# ArduinoDue.net
KiCad netlist of a schematic drawn in Altium Designer
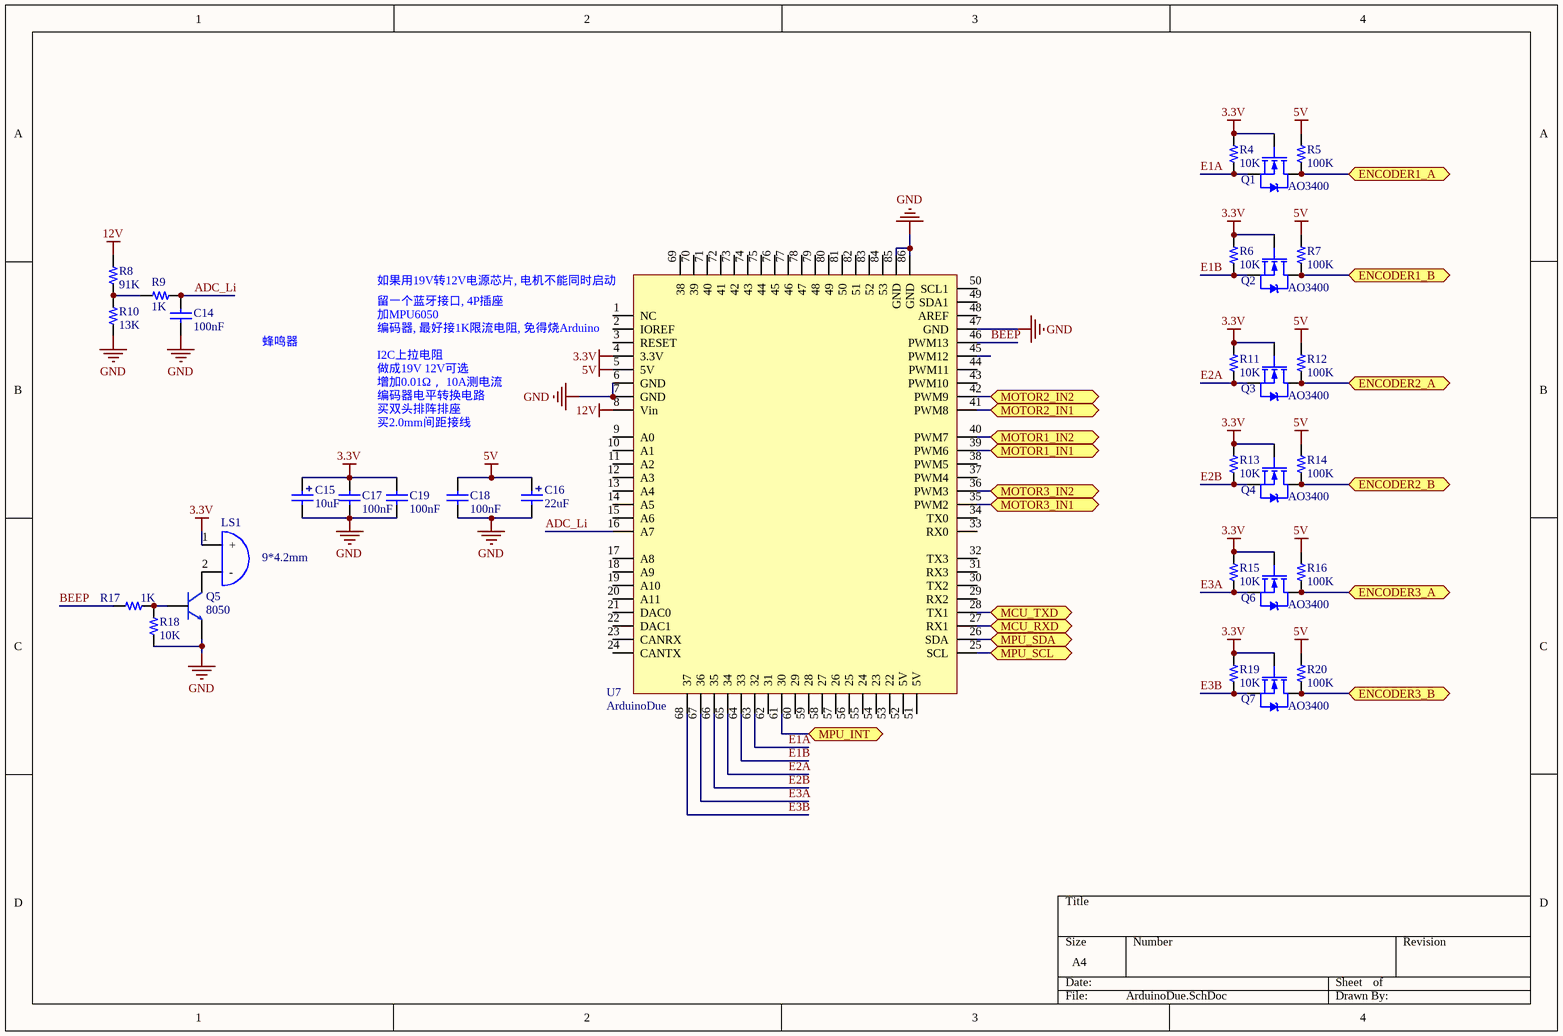
[diagram p0: ArduinoDue.SchDoc]

(export (version "E")
  (design (tool "Eeschema 10.0.6"))
  (components
    (comp (ref "C14")
      (value "100nF")
      (footprint "dq - 0402")
      (description "Capacitor")
      (fields (field (name "Comment") "Cap") (field (name "PUBLISHER") "Altium Limited"))
      (libsource (lib "weifengdq") (part "DQ_Cap"))
    )
    (comp (ref "C15")
      (value "10uF")
      (footprint "3216-18")
      (description "Capacitor")
      (fields (field (name "Comment") "Cap_Pol") (field (name "PUBLISHER") "Altium Limited"))
      (libsource (lib "weifengdq") (part "Cap_Pol"))
    )
    (comp (ref "C16")
      (value "22uF")
      (footprint "3528-21")
      (description "Capacitor")
      (fields (field (name "Comment") "Cap_Pol") (field (name "PUBLISHER") "Altium Limited"))
      (libsource (lib "weifengdq") (part "Cap_Pol"))
    )
    (comp (ref "C17")
      (value "100nF")
      (footprint "dq - 0402")
      (description "Capacitor")
      (fields (field (name "Comment") "Cap") (field (name "PUBLISHER") "Altium Limited"))
      (libsource (lib "weifengdq") (part "DQ_Cap"))
    )
    (comp (ref "C18")
      (value "100nF")
      (footprint "dq - 0402")
      (description "Capacitor")
      (fields (field (name "Comment") "Cap") (field (name "PUBLISHER") "Altium Limited"))
      (libsource (lib "weifengdq") (part "DQ_Cap"))
    )
    (comp (ref "C19")
      (value "100nF")
      (footprint "dq - 0402")
      (description "Capacitor")
      (fields (field (name "Comment") "Cap") (field (name "PUBLISHER") "Altium Limited"))
      (libsource (lib "weifengdq") (part "DQ_Cap"))
    )
    (comp (ref "LS1")
      (value "9*4.2mm")
      (footprint "BUZZER-9*4.2MM")
      (description "Electrical Bell")
      (fields (field (name "PUBLISHER") "Altium Limited"))
      (libsource (lib "weifengdq") (part "Buzzer_1"))
    )
    (comp (ref "Q1")
      (value "AO3400")
      (footprint "SOT-23-3 - AO3400")
      (description "N-Channel Power MOSFET")
      (fields (field (name "PUBLISHER") "Altium Limited"))
      (libsource (lib "weifengdq") (part "NMOS"))
    )
    (comp (ref "Q2")
      (value "AO3400")
      (footprint "SOT-23-3 - AO3400")
      (description "N-Channel Power MOSFET")
      (fields (field (name "PUBLISHER") "Altium Limited"))
      (libsource (lib "weifengdq") (part "NMOS"))
    )
    (comp (ref "Q3")
      (value "AO3400")
      (footprint "SOT-23-3 - AO3400")
      (description "N-Channel Power MOSFET")
      (fields (field (name "PUBLISHER") "Altium Limited"))
      (libsource (lib "weifengdq") (part "NMOS"))
    )
    (comp (ref "Q4")
      (value "AO3400")
      (footprint "SOT-23-3 - AO3400")
      (description "N-Channel Power MOSFET")
      (fields (field (name "PUBLISHER") "Altium Limited"))
      (libsource (lib "weifengdq") (part "NMOS"))
    )
    (comp (ref "Q5") (value "8050") (footprint "SOT-23-3") (libsource (lib "weifengdq") (part "NPN")))
    (comp (ref "Q6")
      (value "AO3400")
      (footprint "SOT-23-3 - AO3400")
      (description "N-Channel Power MOSFET")
      (fields (field (name "PUBLISHER") "Altium Limited"))
      (libsource (lib "weifengdq") (part "NMOS"))
    )
    (comp (ref "Q7")
      (value "AO3400")
      (footprint "SOT-23-3 - AO3400")
      (description "N-Channel Power MOSFET")
      (fields (field (name "PUBLISHER") "Altium Limited"))
      (libsource (lib "weifengdq") (part "NMOS"))
    )
    (comp (ref "R4")
      (value "10K")
      (footprint "dq - 0402")
      (description "Resistance")
      (fields (field (name "Comment") "Res"))
      (libsource (lib "weifengdq") (part "DQ_Res"))
    )
    (comp (ref "R5")
      (value "100K")
      (footprint "dq - 0402")
      (description "Resistance")
      (fields (field (name "Comment") "Res"))
      (libsource (lib "weifengdq") (part "DQ_Res"))
    )
    (comp (ref "R6")
      (value "10K")
      (footprint "dq - 0402")
      (description "Resistance")
      (fields (field (name "Comment") "Res"))
      (libsource (lib "weifengdq") (part "DQ_Res"))
    )
    (comp (ref "R7")
      (value "100K")
      (footprint "dq - 0402")
      (description "Resistance")
      (fields (field (name "Comment") "Res"))
      (libsource (lib "weifengdq") (part "DQ_Res"))
    )
    (comp (ref "R8")
      (value "91K")
      (footprint "dq - 0402")
      (description "Resistance")
      (fields (field (name "Comment") "Res"))
      (libsource (lib "weifengdq") (part "DQ_Res"))
    )
    (comp (ref "R9")
      (value "1K")
      (footprint "dq - 0402")
      (description "Resistance")
      (fields (field (name "Comment") "Res"))
      (libsource (lib "weifengdq") (part "DQ_Res"))
    )
    (comp (ref "R10")
      (value "13K")
      (footprint "dq - 0402")
      (description "Resistance")
      (fields (field (name "Comment") "Res"))
      (libsource (lib "weifengdq") (part "DQ_Res"))
    )
    (comp (ref "R11")
      (value "10K")
      (footprint "dq - 0402")
      (description "Resistance")
      (fields (field (name "Comment") "Res"))
      (libsource (lib "weifengdq") (part "DQ_Res"))
    )
    (comp (ref "R12")
      (value "100K")
      (footprint "dq - 0402")
      (description "Resistance")
      (fields (field (name "Comment") "Res"))
      (libsource (lib "weifengdq") (part "DQ_Res"))
    )
    (comp (ref "R13")
      (value "10K")
      (footprint "dq - 0402")
      (description "Resistance")
      (fields (field (name "Comment") "Res"))
      (libsource (lib "weifengdq") (part "DQ_Res"))
    )
    (comp (ref "R14")
      (value "100K")
      (footprint "dq - 0402")
      (description "Resistance")
      (fields (field (name "Comment") "Res"))
      (libsource (lib "weifengdq") (part "DQ_Res"))
    )
    (comp (ref "R15")
      (value "10K")
      (footprint "dq - 0402")
      (description "Resistance")
      (fields (field (name "Comment") "Res"))
      (libsource (lib "weifengdq") (part "DQ_Res"))
    )
    (comp (ref "R16")
      (value "100K")
      (footprint "dq - 0402")
      (description "Resistance")
      (fields (field (name "Comment") "Res"))
      (libsource (lib "weifengdq") (part "DQ_Res"))
    )
    (comp (ref "R17")
      (value "1K")
      (footprint "dq - 0402")
      (description "Resistance")
      (fields (field (name "Comment") "Res"))
      (libsource (lib "weifengdq") (part "DQ_Res"))
    )
    (comp (ref "R18")
      (value "10K")
      (footprint "dq - 0402")
      (description "Resistance")
      (fields (field (name "Comment") "Res"))
      (libsource (lib "weifengdq") (part "DQ_Res"))
    )
    (comp (ref "R19")
      (value "10K")
      (footprint "dq - 0402")
      (description "Resistance")
      (fields (field (name "Comment") "Res"))
      (libsource (lib "weifengdq") (part "DQ_Res"))
    )
    (comp (ref "R20")
      (value "100K")
      (footprint "dq - 0402")
      (description "Resistance")
      (fields (field (name "Comment") "Res"))
      (libsource (lib "weifengdq") (part "DQ_Res"))
    )
    (comp (ref "U7")
      (value "ArduinoDue")
      (footprint "ArduinoDue")
      (libsource (lib "weifengdq") (part "ArduinoDue"))
    )
  )
  (nets
    (net (code "1") (name "/ADC_Li") (class "Default")
      (node (ref "C14") (pin "2") (pinfunction "2_2") (pintype "passive"))
      (node (ref "R9") (pin "2") (pintype "passive"))
      (node (ref "U7") (pin "16") (pinfunction "A7_16") (pintype "passive"))
    )
    (net (code "2") (name "/BEEP") (class "Default")
      (node (ref "R17") (pin "2") (pintype "passive"))
      (node (ref "U7") (pin "46") (pinfunction "PWM13_46") (pintype "passive"))
    )
    (net (code "3") (name "/E1A") (class "Default")
      (node (ref "Q1") (pin "3") (pinfunction "S_3") (pintype "passive"))
      (node (ref "R4") (pin "2") (pintype "passive"))
      (node (ref "U7") (pin "63") (pinfunction "32_63") (pintype "passive"))
    )
    (net (code "4") (name "/E1B") (class "Default")
      (node (ref "Q2") (pin "3") (pinfunction "S_3") (pintype "passive"))
      (node (ref "R6") (pin "2") (pintype "passive"))
      (node (ref "U7") (pin "64") (pinfunction "33_64") (pintype "passive"))
    )
    (net (code "5") (name "/E2A") (class "Default")
      (node (ref "Q3") (pin "3") (pinfunction "S_3") (pintype "passive"))
      (node (ref "R11") (pin "2") (pintype "passive"))
      (node (ref "U7") (pin "65") (pinfunction "34_65") (pintype "passive"))
    )
    (net (code "6") (name "/E2B") (class "Default")
      (node (ref "Q4") (pin "3") (pinfunction "S_3") (pintype "passive"))
      (node (ref "R13") (pin "2") (pintype "passive"))
      (node (ref "U7") (pin "66") (pinfunction "35_66") (pintype "passive"))
    )
    (net (code "7") (name "/E3A") (class "Default")
      (node (ref "Q6") (pin "3") (pinfunction "S_3") (pintype "passive"))
      (node (ref "R15") (pin "2") (pintype "passive"))
      (node (ref "U7") (pin "67") (pinfunction "36_67") (pintype "passive"))
    )
    (net (code "8") (name "/E3B") (class "Default")
      (node (ref "Q7") (pin "3") (pinfunction "S_3") (pintype "passive"))
      (node (ref "R19") (pin "2") (pintype "passive"))
      (node (ref "U7") (pin "68") (pinfunction "37_68") (pintype "passive"))
    )
    (net (code "9") (name "/ENCODER1_A") (class "Default")
      (node (ref "Q1") (pin "2") (pinfunction "D_2") (pintype "passive"))
      (node (ref "R5") (pin "2") (pintype "passive"))
    )
    (net (code "10") (name "/ENCODER1_B") (class "Default")
      (node (ref "Q2") (pin "2") (pinfunction "D_2") (pintype "passive"))
      (node (ref "R7") (pin "2") (pintype "passive"))
    )
    (net (code "11") (name "/ENCODER2_A") (class "Default")
      (node (ref "Q3") (pin "2") (pinfunction "D_2") (pintype "passive"))
      (node (ref "R12") (pin "2") (pintype "passive"))
    )
    (net (code "12") (name "/ENCODER2_B") (class "Default")
      (node (ref "Q4") (pin "2") (pinfunction "D_2") (pintype "passive"))
      (node (ref "R14") (pin "2") (pintype "passive"))
    )
    (net (code "13") (name "/ENCODER3_A") (class "Default")
      (node (ref "Q6") (pin "2") (pinfunction "D_2") (pintype "passive"))
      (node (ref "R16") (pin "2") (pintype "passive"))
    )
    (net (code "14") (name "/ENCODER3_B") (class "Default")
      (node (ref "Q7") (pin "2") (pinfunction "D_2") (pintype "passive"))
      (node (ref "R20") (pin "2") (pintype "passive"))
    )
    (net (code "15") (name "/MCU_RXD") (class "Default")
      (node (ref "U7") (pin "27") (pinfunction "RX1_27") (pintype "passive"))
    )
    (net (code "16") (name "/MCU_TXD") (class "Default")
      (node (ref "U7") (pin "28") (pinfunction "TX1_28") (pintype "passive"))
    )
    (net (code "17") (name "/MOTOR1_IN1") (class "Default")
      (node (ref "U7") (pin "39") (pinfunction "PWM6_39") (pintype "passive"))
    )
    (net (code "18") (name "/MOTOR1_IN2") (class "Default")
      (node (ref "U7") (pin "40") (pinfunction "PWM7_40") (pintype "passive"))
    )
    (net (code "19") (name "/MOTOR2_IN1") (class "Default")
      (node (ref "U7") (pin "41") (pinfunction "PWM8_41") (pintype "passive"))
    )
    (net (code "20") (name "/MOTOR2_IN2") (class "Default")
      (node (ref "U7") (pin "42") (pinfunction "PWM9_42") (pintype "passive"))
    )
    (net (code "21") (name "/MOTOR3_IN1") (class "Default")
      (node (ref "U7") (pin "35") (pinfunction "PWM2_35") (pintype "passive"))
    )
    (net (code "22") (name "/MOTOR3_IN2") (class "Default")
      (node (ref "U7") (pin "36") (pinfunction "PWM3_36") (pintype "passive"))
    )
    (net (code "23") (name "/MPU_INT") (class "Default")
      (node (ref "U7") (pin "61") (pinfunction "30_61") (pintype "passive"))
    )
    (net (code "24") (name "/MPU_SCL") (class "Default")
      (node (ref "U7") (pin "25") (pinfunction "SCL_25") (pintype "passive"))
    )
    (net (code "25") (name "/MPU_SDA") (class "Default")
      (node (ref "U7") (pin "26") (pinfunction "SDA_26") (pintype "passive"))
    )
    (net (code "26") (name "3.3V") (class "Default")
      (node (ref "C15") (pin "1") (pinfunction "1_1") (pintype "passive"))
      (node (ref "C17") (pin "2") (pinfunction "2_2") (pintype "passive"))
      (node (ref "C19") (pin "2") (pinfunction "2_2") (pintype "passive"))
      (node (ref "LS1") (pin "1") (pinfunction "+_1") (pintype "passive"))
      (node (ref "Q1") (pin "1") (pinfunction "G_1") (pintype "passive"))
      (node (ref "Q2") (pin "1") (pinfunction "G_1") (pintype "passive"))
      (node (ref "Q3") (pin "1") (pinfunction "G_1") (pintype "passive"))
      (node (ref "Q4") (pin "1") (pinfunction "G_1") (pintype "passive"))
      (node (ref "Q6") (pin "1") (pinfunction "G_1") (pintype "passive"))
      (node (ref "Q7") (pin "1") (pinfunction "G_1") (pintype "passive"))
      (node (ref "R11") (pin "1") (pintype "passive"))
      (node (ref "R13") (pin "1") (pintype "passive"))
      (node (ref "R15") (pin "1") (pintype "passive"))
      (node (ref "R19") (pin "1") (pintype "passive"))
      (node (ref "R4") (pin "1") (pintype "passive"))
      (node (ref "R6") (pin "1") (pintype "passive"))
      (node (ref "U7") (pin "4") (pinfunction "3.3V_4") (pintype "passive"))
    )
    (net (code "27") (name "5V") (class "Default")
      (node (ref "C16") (pin "1") (pinfunction "1_1") (pintype "passive"))
      (node (ref "C18") (pin "2") (pinfunction "2_2") (pintype "passive"))
      (node (ref "R12") (pin "1") (pintype "passive"))
      (node (ref "R14") (pin "1") (pintype "passive"))
      (node (ref "R16") (pin "1") (pintype "passive"))
      (node (ref "R20") (pin "1") (pintype "passive"))
      (node (ref "R5") (pin "1") (pintype "passive"))
      (node (ref "R7") (pin "1") (pintype "passive"))
      (node (ref "U7") (pin "5") (pinfunction "5V_5") (pintype "passive"))
    )
    (net (code "28") (name "12V") (class "Default")
      (node (ref "R8") (pin "1") (pintype "passive"))
      (node (ref "U7") (pin "8") (pinfunction "Vin_8") (pintype "passive"))
    )
    (net (code "29") (name "GND") (class "Default")
      (node (ref "C14") (pin "1") (pinfunction "1_1") (pintype "passive"))
      (node (ref "C15") (pin "2") (pinfunction "2_2") (pintype "passive"))
      (node (ref "C16") (pin "2") (pinfunction "2_2") (pintype "passive"))
      (node (ref "C17") (pin "1") (pinfunction "1_1") (pintype "passive"))
      (node (ref "C18") (pin "1") (pinfunction "1_1") (pintype "passive"))
      (node (ref "C19") (pin "1") (pinfunction "1_1") (pintype "passive"))
      (node (ref "Q5") (pin "1") (pinfunction "e_1") (pintype "passive"))
      (node (ref "R10") (pin "2") (pintype "passive"))
      (node (ref "R18") (pin "2") (pintype "passive"))
      (node (ref "U7") (pin "47") (pinfunction "GND_47") (pintype "passive"))
      (node (ref "U7") (pin "6") (pinfunction "GND_6") (pintype "passive"))
      (node (ref "U7") (pin "7") (pinfunction "GND_7") (pintype "passive"))
      (node (ref "U7") (pin "85") (pinfunction "GND_85") (pintype "passive"))
      (node (ref "U7") (pin "86") (pinfunction "GND_86") (pintype "passive"))
    )
    (net (code "30") (name "Net-(LS1--)") (class "Default")
      (node (ref "LS1") (pin "2") (pinfunction "-_2") (pintype "passive"))
      (node (ref "Q5") (pin "3") (pinfunction "c_3") (pintype "passive"))
    )
    (net (code "31") (name "Net-(Q5-b)") (class "Default")
      (node (ref "Q5") (pin "2") (pinfunction "b_2") (pintype "passive"))
      (node (ref "R17") (pin "1") (pintype "passive"))
      (node (ref "R18") (pin "1") (pintype "passive"))
    )
    (net (code "32") (name "Net-(R10-Pad1)") (class "Default")
      (node (ref "R10") (pin "1") (pintype "passive"))
      (node (ref "R8") (pin "2") (pintype "passive"))
      (node (ref "R9") (pin "1") (pintype "passive"))
    )
    (net (code "33") (name "unconnected-(U7-5V-Pad51)") (class "Default")
      (node (ref "U7") (pin "51") (pinfunction "5V_51") (pintype "passive"))
    )
    (net (code "34") (name "unconnected-(U7-5V-Pad52)") (class "Default")
      (node (ref "U7") (pin "52") (pinfunction "5V_52") (pintype "passive"))
    )
    (net (code "35") (name "unconnected-(U7-22-Pad53)") (class "Default")
      (node (ref "U7") (pin "53") (pinfunction "22_53") (pintype "passive"))
    )
    (net (code "36") (name "unconnected-(U7-23-Pad54)") (class "Default")
      (node (ref "U7") (pin "54") (pinfunction "23_54") (pintype "passive"))
    )
    (net (code "37") (name "unconnected-(U7-24-Pad55)") (class "Default")
      (node (ref "U7") (pin "55") (pinfunction "24_55") (pintype "passive"))
    )
    (net (code "38") (name "unconnected-(U7-25-Pad56)") (class "Default")
      (node (ref "U7") (pin "56") (pinfunction "25_56") (pintype "passive"))
    )
    (net (code "39") (name "unconnected-(U7-26-Pad57)") (class "Default")
      (node (ref "U7") (pin "57") (pinfunction "26_57") (pintype "passive"))
    )
    (net (code "40") (name "unconnected-(U7-27-Pad58)") (class "Default")
      (node (ref "U7") (pin "58") (pinfunction "27_58") (pintype "passive"))
    )
    (net (code "41") (name "unconnected-(U7-28-Pad59)") (class "Default")
      (node (ref "U7") (pin "59") (pinfunction "28_59") (pintype "passive"))
    )
    (net (code "42") (name "unconnected-(U7-29-Pad60)") (class "Default")
      (node (ref "U7") (pin "60") (pinfunction "29_60") (pintype "passive"))
    )
    (net (code "43") (name "unconnected-(U7-31-Pad62)") (class "Default")
      (node (ref "U7") (pin "62") (pinfunction "31_62") (pintype "passive"))
    )
    (net (code "44") (name "unconnected-(U7-38-Pad69)") (class "Default")
      (node (ref "U7") (pin "69") (pinfunction "38_69") (pintype "passive"))
    )
    (net (code "45") (name "unconnected-(U7-39-Pad70)") (class "Default")
      (node (ref "U7") (pin "70") (pinfunction "39_70") (pintype "passive"))
    )
    (net (code "46") (name "unconnected-(U7-40-Pad71)") (class "Default")
      (node (ref "U7") (pin "71") (pinfunction "40_71") (pintype "passive"))
    )
    (net (code "47") (name "unconnected-(U7-41-Pad72)") (class "Default")
      (node (ref "U7") (pin "72") (pinfunction "41_72") (pintype "passive"))
    )
    (net (code "48") (name "unconnected-(U7-42-Pad73)") (class "Default")
      (node (ref "U7") (pin "73") (pinfunction "42_73") (pintype "passive"))
    )
    (net (code "49") (name "unconnected-(U7-43-Pad74)") (class "Default")
      (node (ref "U7") (pin "74") (pinfunction "43_74") (pintype "passive"))
    )
    (net (code "50") (name "unconnected-(U7-44-Pad75)") (class "Default")
      (node (ref "U7") (pin "75") (pinfunction "44_75") (pintype "passive"))
    )
    (net (code "51") (name "unconnected-(U7-45-Pad76)") (class "Default")
      (node (ref "U7") (pin "76") (pinfunction "45_76") (pintype "passive"))
    )
    (net (code "52") (name "unconnected-(U7-46-Pad77)") (class "Default")
      (node (ref "U7") (pin "77") (pinfunction "46_77") (pintype "passive"))
    )
    (net (code "53") (name "unconnected-(U7-47-Pad78)") (class "Default")
      (node (ref "U7") (pin "78") (pinfunction "47_78") (pintype "passive"))
    )
    (net (code "54") (name "unconnected-(U7-48-Pad79)") (class "Default")
      (node (ref "U7") (pin "79") (pinfunction "48_79") (pintype "passive"))
    )
    (net (code "55") (name "unconnected-(U7-49-Pad80)") (class "Default")
      (node (ref "U7") (pin "80") (pinfunction "49_80") (pintype "passive"))
    )
    (net (code "56") (name "unconnected-(U7-50-Pad81)") (class "Default")
      (node (ref "U7") (pin "81") (pinfunction "50_81") (pintype "passive"))
    )
    (net (code "57") (name "unconnected-(U7-51-Pad82)") (class "Default")
      (node (ref "U7") (pin "82") (pinfunction "51_82") (pintype "passive"))
    )
    (net (code "58") (name "unconnected-(U7-52-Pad83)") (class "Default")
      (node (ref "U7") (pin "83") (pinfunction "52_83") (pintype "passive"))
    )
    (net (code "59") (name "unconnected-(U7-53-Pad84)") (class "Default")
      (node (ref "U7") (pin "84") (pinfunction "53_84") (pintype "passive"))
    )
    (net (code "60") (name "unconnected-(U7-A0-Pad9)") (class "Default")
      (node (ref "U7") (pin "9") (pinfunction "A0_9") (pintype "passive"))
    )
    (net (code "61") (name "unconnected-(U7-A1-Pad10)") (class "Default")
      (node (ref "U7") (pin "10") (pinfunction "A1_10") (pintype "passive"))
    )
    (net (code "62") (name "unconnected-(U7-A2-Pad11)") (class "Default")
      (node (ref "U7") (pin "11") (pinfunction "A2_11") (pintype "passive"))
    )
    (net (code "63") (name "unconnected-(U7-A3-Pad12)") (class "Default")
      (node (ref "U7") (pin "12") (pinfunction "A3_12") (pintype "passive"))
    )
    (net (code "64") (name "unconnected-(U7-A4-Pad13)") (class "Default")
      (node (ref "U7") (pin "13") (pinfunction "A4_13") (pintype "passive"))
    )
    (net (code "65") (name "unconnected-(U7-A5-Pad14)") (class "Default")
      (node (ref "U7") (pin "14") (pinfunction "A5_14") (pintype "passive"))
    )
    (net (code "66") (name "unconnected-(U7-A6-Pad15)") (class "Default")
      (node (ref "U7") (pin "15") (pinfunction "A6_15") (pintype "passive"))
    )
    (net (code "67") (name "unconnected-(U7-A8-Pad17)") (class "Default")
      (node (ref "U7") (pin "17") (pinfunction "A8_17") (pintype "passive"))
    )
    (net (code "68") (name "unconnected-(U7-A9-Pad18)") (class "Default")
      (node (ref "U7") (pin "18") (pinfunction "A9_18") (pintype "passive"))
    )
    (net (code "69") (name "unconnected-(U7-A10-Pad19)") (class "Default")
      (node (ref "U7") (pin "19") (pinfunction "A10_19") (pintype "passive"))
    )
    (net (code "70") (name "unconnected-(U7-A11-Pad20)") (class "Default")
      (node (ref "U7") (pin "20") (pinfunction "A11_20") (pintype "passive"))
    )
    (net (code "71") (name "unconnected-(U7-AREF-Pad48)") (class "Default")
      (node (ref "U7") (pin "48") (pinfunction "AREF_48") (pintype "passive"))
    )
    (net (code "72") (name "unconnected-(U7-CANRX-Pad23)") (class "Default")
      (node (ref "U7") (pin "23") (pinfunction "CANRX_23") (pintype "passive"))
    )
    (net (code "73") (name "unconnected-(U7-CANTX-Pad24)") (class "Default")
      (node (ref "U7") (pin "24") (pinfunction "CANTX_24") (pintype "passive"))
    )
    (net (code "74") (name "unconnected-(U7-DAC0-Pad21)") (class "Default")
      (node (ref "U7") (pin "21") (pinfunction "DAC0_21") (pintype "passive"))
    )
    (net (code "75") (name "unconnected-(U7-DAC1-Pad22)") (class "Default")
      (node (ref "U7") (pin "22") (pinfunction "DAC1_22") (pintype "passive"))
    )
    (net (code "76") (name "unconnected-(U7-IOREF-Pad2)") (class "Default")
      (node (ref "U7") (pin "2") (pinfunction "IOREF_2") (pintype "passive"))
    )
    (net (code "77") (name "unconnected-(U7-NC-Pad1)") (class "Default")
      (node (ref "U7") (pin "1") (pinfunction "NC_1") (pintype "passive"))
    )
    (net (code "78") (name "unconnected-(U7-PWM4-Pad37)") (class "Default")
      (node (ref "U7") (pin "37") (pinfunction "PWM4_37") (pintype "passive"))
    )
    (net (code "79") (name "unconnected-(U7-PWM5-Pad38)") (class "Default")
      (node (ref "U7") (pin "38") (pinfunction "PWM5_38") (pintype "passive"))
    )
    (net (code "80") (name "unconnected-(U7-PWM10-Pad43)") (class "Default")
      (node (ref "U7") (pin "43") (pinfunction "PWM10_43") (pintype "passive"))
    )
    (net (code "81") (name "unconnected-(U7-PWM11-Pad44)") (class "Default")
      (node (ref "U7") (pin "44") (pinfunction "PWM11_44") (pintype "passive"))
    )
    (net (code "82") (name "unconnected-(U7-PWM12-Pad45)") (class "Default")
      (node (ref "U7") (pin "45") (pinfunction "PWM12_45") (pintype "passive"))
    )
    (net (code "83") (name "unconnected-(U7-RESET-Pad3)") (class "Default")
      (node (ref "U7") (pin "3") (pinfunction "RESET_3") (pintype "passive"))
    )
    (net (code "84") (name "unconnected-(U7-RX0-Pad33)") (class "Default")
      (node (ref "U7") (pin "33") (pinfunction "RX0_33") (pintype "passive"))
    )
    (net (code "85") (name "unconnected-(U7-RX2-Pad29)") (class "Default")
      (node (ref "U7") (pin "29") (pinfunction "RX2_29") (pintype "passive"))
    )
    (net (code "86") (name "unconnected-(U7-RX3-Pad31)") (class "Default")
      (node (ref "U7") (pin "31") (pinfunction "RX3_31") (pintype "passive"))
    )
    (net (code "87") (name "unconnected-(U7-SCL1-Pad50)") (class "Default")
      (node (ref "U7") (pin "50") (pinfunction "SCL1_50") (pintype "passive"))
    )
    (net (code "88") (name "unconnected-(U7-SDA1-Pad49)") (class "Default")
      (node (ref "U7") (pin "49") (pinfunction "SDA1_49") (pintype "passive"))
    )
    (net (code "89") (name "unconnected-(U7-TX0-Pad34)") (class "Default")
      (node (ref "U7") (pin "34") (pinfunction "TX0_34") (pintype "passive"))
    )
    (net (code "90") (name "unconnected-(U7-TX2-Pad30)") (class "Default")
      (node (ref "U7") (pin "30") (pinfunction "TX2_30") (pintype "passive"))
    )
    (net (code "91") (name "unconnected-(U7-TX3-Pad32)") (class "Default")
      (node (ref "U7") (pin "32") (pinfunction "TX3_32") (pintype "passive"))
    )
  )
)
